# Proxxon.net
KiCad netlist of a schematic drawn in Altium Designer
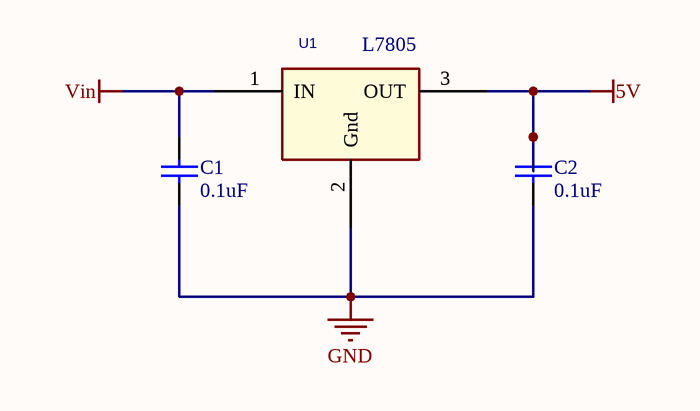
[diagram p0: Proxxon.SchDoc]

(export (version "E")
  (design (tool "Eeschema 10.0.6"))
  (components
    (comp (ref "C1")
      (value "0.1uF")
      (footprint "CERCAP SMD0603L (IPC1608L)")
      (description "Capacitor (Semiconductor SIM Model)")
      (fields (field (name "PUBLISHER") "Altium Limited"))
      (libsource (lib "Miscellaneous Devices") (part "Cap Semi"))
    )
    (comp (ref "C2")
      (value "0.1uF")
      (footprint "CERCAP SMD0603L (IPC1608L)")
      (description "Capacitor (Semiconductor SIM Model)")
      (fields (field (name "PUBLISHER") "Altium Limited"))
      (libsource (lib "Miscellaneous Devices") (part "Cap Semi"))
    )
    (comp (ref "U1") (value "L7805") (footprint "DPAK - duplicate") (libsource (lib "*") (part "7805")))
  )
  (nets
    (net (code "1") (name "5V") (class "Default")
      (node (ref "C2") (pin "1") (pinfunction "1_1") (pintype "passive"))
      (node (ref "U1") (pin "3") (pinfunction "OUT_3") (pintype "passive"))
    )
    (net (code "2") (name "GND") (class "Default")
      (node (ref "C1") (pin "2") (pinfunction "2_2") (pintype "passive"))
      (node (ref "C2") (pin "2") (pinfunction "2_2") (pintype "passive"))
      (node (ref "U1") (pin "2") (pinfunction "Gnd_2") (pintype "passive"))
    )
    (net (code "3") (name "Vin") (class "Default")
      (node (ref "C1") (pin "1") (pinfunction "1_1") (pintype "passive"))
      (node (ref "U1") (pin "1") (pinfunction "IN_1") (pintype "passive"))
    )
  )
)
